# MMC-CAN.net
KiCad netlist of a schematic drawn in Altium Designer
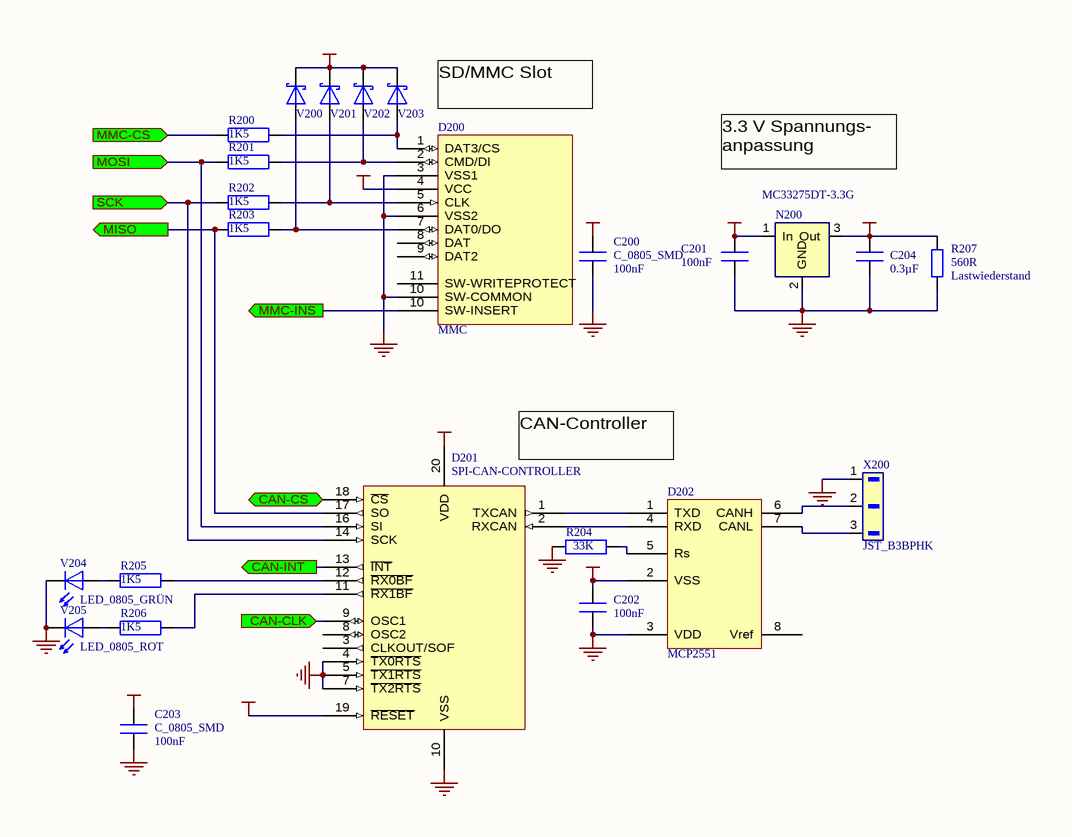
[diagram p0: MMC-CAN.SchDoc]

(export (version "E")
  (design (tool "Eeschema 10.0.6"))
  (components
    (comp (ref "C200")
      (value "C_0805_SMD")
      (footprint "0805_R")
      (description "Kondensator in SMD-Bauform")
      (fields (field (name "ALTIUM_UNNAMED_1") "100nF"))
      (libsource (lib "Kondensatoren") (part "C_0805_SMD"))
    )
    (comp (ref "C201")
      (value "C_0805_SMD")
      (footprint "0805_R")
      (description "Kondensator in SMD-Bauform")
      (fields (field (name "ALTIUM_UNNAMED_1") "100nF"))
      (libsource (lib "Kondensatoren") (part "C_0805_SMD"))
    )
    (comp (ref "C202")
      (value "C_0805_SMD")
      (footprint "0805_R")
      (description "Kondensator in SMD-Bauform")
      (fields (field (name "ALTIUM_UNNAMED_1") "100nF"))
      (libsource (lib "Kondensatoren") (part "C_0805_SMD"))
    )
    (comp (ref "C203")
      (value "C_0805_SMD")
      (footprint "0805_R")
      (description "Kondensator in SMD-Bauform")
      (fields (field (name "ALTIUM_UNNAMED_1") "100nF"))
      (libsource (lib "Kondensatoren") (part "C_0805_SMD"))
    )
    (comp (ref "C204")
      (value "C_1206_SMD")
      (footprint "1206_R")
      (description "Kondensator in SMD-Bauform")
      (fields (field (name "ALTIUM_UNNAMED_1") "0.3µF"))
      (libsource (lib "Kondensatoren") (part "C_1206_SMD"))
    )
    (comp (ref "D200") (value "MMC") (libsource (lib "Vorbereitung") (part "MMC")))
    (comp (ref "D201") (value "SPI-CAN-CONTROLLER") (libsource (lib "Vorbereitung") (part "MCP2515")))
    (comp (ref "D202") (value "MCP2551") (libsource (lib "Vorbereitung") (part "MCP2551")))
    (comp (ref "N200")
      (value "MC33275DT-3.3G")
      (footprint "DPAK_R")
      (description "MC33275DT-3.3G_SMD_3.3V Festspannungsregler positiv")
      (libsource (lib "Spannungsregler_SMD") (part "MC33275DT-3.3G_SMD"))
    )
    (comp (ref "R200")
      (value "R_0805_SMD")
      (footprint "0805_R")
      (description "Widerstand")
      (fields (field (name "ALTIUM_UNNAMED_1") "1K5"))
      (libsource (lib "Widerstände") (part "R_0805_SMD"))
    )
    (comp (ref "R201")
      (value "R_0805_SMD")
      (footprint "0805_R")
      (description "Widerstand")
      (fields (field (name "ALTIUM_UNNAMED_1") "1K5"))
      (libsource (lib "Widerstände") (part "R_0805_SMD"))
    )
    (comp (ref "R202")
      (value "R_0805_SMD")
      (footprint "0805_R")
      (description "Widerstand")
      (fields (field (name "ALTIUM_UNNAMED_1") "1K5"))
      (libsource (lib "Widerstände") (part "R_0805_SMD"))
    )
    (comp (ref "R203")
      (value "R_0805_SMD")
      (footprint "0805_R")
      (description "Widerstand")
      (fields (field (name "ALTIUM_UNNAMED_1") "1K5"))
      (libsource (lib "Widerstände") (part "R_0805_SMD"))
    )
    (comp (ref "R204")
      (value "R_0805_SMD")
      (footprint "0805_R")
      (description "Widerstand")
      (fields (field (name "ALTIUM_UNNAMED_1") "33K"))
      (libsource (lib "Widerstände") (part "R_0805_SMD"))
    )
    (comp (ref "R205")
      (value "R_0805_SMD")
      (footprint "0805_R")
      (description "Widerstand")
      (fields (field (name "ALTIUM_UNNAMED_1") "1K5"))
      (libsource (lib "Widerstände") (part "R_0805_SMD"))
    )
    (comp (ref "R206")
      (value "R_0805_SMD")
      (footprint "0805_R")
      (description "Widerstand")
      (fields (field (name "ALTIUM_UNNAMED_1") "1K5"))
      (libsource (lib "Widerstände") (part "R_0805_SMD"))
    )
    (comp (ref "R207")
      (value "Lastwiederstand")
      (footprint "CR2012-0805")
      (description "Resistor")
      (fields (field (name "ALTIUM_VALUE") "560R") (field (name "PUBLISHER") "Altium Limited"))
      (libsource (lib "Miscellaneous Devices") (part "Res2"))
    )
    (comp (ref "V200")
      (value "SCHOTTKY_SMC_SMD")
      (footprint "CR2012-0805")
      (description "SCHOTTKY-Diode_SMC_SMD")
      (libsource (lib "Dioden") (part "SCHOTTKY_SMC_SMD"))
    )
    (comp (ref "V201")
      (value "SCHOTTKY_SMC_SMD")
      (footprint "CR2012-0805")
      (description "SCHOTTKY-Diode_SMC_SMD")
      (libsource (lib "Dioden") (part "SCHOTTKY_SMC_SMD"))
    )
    (comp (ref "V202")
      (value "SCHOTTKY_SMC_SMD")
      (footprint "CR2012-0805")
      (description "SCHOTTKY-Diode_SMC_SMD")
      (libsource (lib "Dioden") (part "SCHOTTKY_SMC_SMD"))
    )
    (comp (ref "V203")
      (value "SCHOTTKY_SMC_SMD")
      (footprint "CR2012-0805")
      (description "SCHOTTKY-Diode_SMC_SMD")
      (libsource (lib "Dioden") (part "SCHOTTKY_SMC_SMD"))
    )
    (comp (ref "V204")
      (value "LED_0805_GRÜN")
      (footprint "0805_R")
      (description "Leuchtdiode_SMD_0805")
      (libsource (lib "Konventionel") (part "LED_0805_SMD"))
    )
    (comp (ref "V205")
      (value "LED_0805_ROT")
      (footprint "0805_R")
      (description "Leuchtdiode_SMD_0805")
      (libsource (lib "Konventionel") (part "LED_0805_SMD"))
    )
    (comp (ref "X200")
      (value "JST_B3BPHK")
      (footprint "B3BPHK")
      (description "Buchse_3-polig")
      (libsource (lib "Stecker") (part "JST_B3BPHK"))
    )
  )
  (nets
    (net (code "1") (name "/CAN-CLK") (class "Default")
      (node (ref "D201") (pin "9") (pinfunction "OSC1_9") (pintype "bidirectional"))
    )
    (net (code "2") (name "/CAN-CS") (class "Default")
      (node (ref "D201") (pin "18") (pinfunction "~{CS}_18") (pintype "input"))
    )
    (net (code "3") (name "/CAN-INT") (class "Default")
      (node (ref "D201") (pin "13") (pinfunction "~{INT}_13") (pintype "output"))
    )
    (net (code "4") (name "/MISO") (class "Default")
      (node (ref "D201") (pin "17") (pinfunction "SO_17") (pintype "output"))
      (node (ref "R203") (pin "1") (pinfunction "1_1") (pintype "passive"))
    )
    (net (code "5") (name "/MMC-CS") (class "Default")
      (node (ref "R200") (pin "1") (pinfunction "1_1") (pintype "passive"))
    )
    (net (code "6") (name "/MMC-INS") (class "Default")
      (node (ref "D200") (pin "10") (pinfunction "SW-INSERT_10") (pintype "passive"))
    )
    (net (code "7") (name "/MOSI") (class "Default")
      (node (ref "D201") (pin "16") (pinfunction "SI_16") (pintype "input"))
      (node (ref "R201") (pin "1") (pinfunction "1_1") (pintype "passive"))
    )
    (net (code "8") (name "/SCK") (class "Default")
      (node (ref "D201") (pin "14") (pinfunction "SCK_14") (pintype "input"))
      (node (ref "R202") (pin "1") (pinfunction "1_1") (pintype "passive"))
    )
    (net (code "9") (name "GND") (class "Default")
      (node (ref "C200") (pin "1") (pinfunction "1_1") (pintype "passive"))
      (node (ref "C201") (pin "2") (pinfunction "2_2") (pintype "passive"))
      (node (ref "C202") (pin "1") (pinfunction "1_1") (pintype "passive"))
      (node (ref "C203") (pin "1") (pinfunction "1_1") (pintype "passive"))
      (node (ref "C204") (pin "1") (pinfunction "1_1") (pintype "passive"))
      (node (ref "D200") (pin "10") (pinfunction "SW-COMMON_10") (pintype "passive"))
      (node (ref "D200") (pin "3") (pinfunction "VSS1_3") (pintype "power_in"))
      (node (ref "D200") (pin "6") (pinfunction "VSS2_6") (pintype "power_in"))
      (node (ref "D201") (pin "10") (pinfunction "VSS_10") (pintype "power_in"))
      (node (ref "D201") (pin "4") (pinfunction "~{TX0RTS}_4") (pintype "input"))
      (node (ref "D201") (pin "5") (pinfunction "~{TX1RTS}_5") (pintype "input"))
      (node (ref "D201") (pin "7") (pinfunction "~{TX2RTS}_7") (pintype "input"))
      (node (ref "D202") (pin "3") (pinfunction "VDD_3") (pintype "passive"))
      (node (ref "N200") (pin "2") (pinfunction "GND_2") (pintype "power_in"))
      (node (ref "R204") (pin "1") (pinfunction "1_1") (pintype "passive"))
      (node (ref "R207") (pin "2") (pinfunction "2_2") (pintype "passive"))
      (node (ref "V204") (pin "2") (pinfunction "K_2") (pintype "passive"))
      (node (ref "V205") (pin "2") (pinfunction "K_2") (pintype "passive"))
      (node (ref "X200") (pin "1") (pintype "passive"))
    )
    (net (code "10") (name "Net-(D200-CLK)") (class "Default")
      (node (ref "D200") (pin "5") (pinfunction "CLK_5") (pintype "input"))
      (node (ref "R202") (pin "2") (pinfunction "2_2") (pintype "passive"))
      (node (ref "V201") (pin "1") (pinfunction "A_1") (pintype "passive"))
    )
    (net (code "11") (name "Net-(D200-CMD{slash}DI)") (class "Default")
      (node (ref "D200") (pin "2") (pinfunction "CMD/DI_2") (pintype "bidirectional"))
      (node (ref "R201") (pin "2") (pinfunction "2_2") (pintype "passive"))
      (node (ref "V202") (pin "1") (pinfunction "A_1") (pintype "passive"))
    )
    (net (code "12") (name "Net-(D200-DAT0{slash}DO)") (class "Default")
      (node (ref "D200") (pin "7") (pinfunction "DAT0/DO_7") (pintype "bidirectional"))
      (node (ref "R203") (pin "2") (pinfunction "2_2") (pintype "passive"))
      (node (ref "V200") (pin "1") (pinfunction "A_1") (pintype "passive"))
    )
    (net (code "13") (name "Net-(D200-DAT3{slash}CS)") (class "Default")
      (node (ref "D200") (pin "1") (pinfunction "DAT3/CS_1") (pintype "bidirectional"))
      (node (ref "R200") (pin "2") (pinfunction "2_2") (pintype "passive"))
      (node (ref "V203") (pin "1") (pinfunction "A_1") (pintype "passive"))
    )
    (net (code "14") (name "Net-(D201-RXCAN)") (class "Default")
      (node (ref "D201") (pin "2") (pinfunction "RXCAN_2") (pintype "input"))
      (node (ref "D202") (pin "4") (pinfunction "RXD_4") (pintype "passive"))
    )
    (net (code "15") (name "Net-(D201-TXCAN)") (class "Default")
      (node (ref "D201") (pin "1") (pinfunction "TXCAN_1") (pintype "output"))
      (node (ref "D202") (pin "1") (pinfunction "TXD_1") (pintype "passive"))
    )
    (net (code "16") (name "Net-(D201-~{RX0BF})") (class "Default")
      (node (ref "D201") (pin "12") (pinfunction "~{RX0BF}_12") (pintype "output"))
      (node (ref "R205") (pin "2") (pinfunction "2_2") (pintype "passive"))
    )
    (net (code "17") (name "Net-(D201-~{RX1BF})") (class "Default")
      (node (ref "D201") (pin "11") (pinfunction "~{RX1BF}_11") (pintype "output"))
      (node (ref "R206") (pin "2") (pinfunction "2_2") (pintype "passive"))
    )
    (net (code "18") (name "Net-(D202-CANH)") (class "Default")
      (node (ref "D202") (pin "6") (pinfunction "CANH_6") (pintype "passive"))
      (node (ref "X200") (pin "2") (pintype "passive"))
    )
    (net (code "19") (name "Net-(D202-CANL)") (class "Default")
      (node (ref "D202") (pin "7") (pinfunction "CANL_7") (pintype "passive"))
      (node (ref "X200") (pin "3") (pintype "passive"))
    )
    (net (code "20") (name "Net-(D202-Rs)") (class "Default")
      (node (ref "D202") (pin "5") (pinfunction "Rs_5") (pintype "passive"))
      (node (ref "R204") (pin "2") (pinfunction "2_2") (pintype "passive"))
    )
    (net (code "21") (name "Net-(V204-A)") (class "Default")
      (node (ref "R205") (pin "1") (pinfunction "1_1") (pintype "passive"))
      (node (ref "V204") (pin "1") (pinfunction "A_1") (pintype "passive"))
    )
    (net (code "22") (name "Net-(V205-A)") (class "Default")
      (node (ref "R206") (pin "1") (pinfunction "1_1") (pintype "passive"))
      (node (ref "V205") (pin "1") (pinfunction "A_1") (pintype "passive"))
    )
    (net (code "23") (name "VCC") (class "Default")
      (node (ref "C200") (pin "2") (pinfunction "2_2") (pintype "passive"))
      (node (ref "C201") (pin "1") (pinfunction "1_1") (pintype "passive"))
      (node (ref "C202") (pin "2") (pinfunction "2_2") (pintype "passive"))
      (node (ref "C203") (pin "2") (pinfunction "2_2") (pintype "passive"))
      (node (ref "D201") (pin "19") (pinfunction "~{RESET}_19") (pintype "input"))
      (node (ref "D201") (pin "20") (pinfunction "VDD_20") (pintype "power_in"))
      (node (ref "D202") (pin "2") (pinfunction "VSS_2") (pintype "passive"))
      (node (ref "N200") (pin "1") (pinfunction "In_1") (pintype "power_in"))
    )
    (net (code "24") (name "VCC3V") (class "Default")
      (node (ref "C204") (pin "2") (pinfunction "2_2") (pintype "passive"))
      (node (ref "D200") (pin "4") (pinfunction "VCC_4") (pintype "power_in"))
      (node (ref "N200") (pin "3") (pinfunction "Out_3") (pintype "power_in"))
      (node (ref "R207") (pin "1") (pinfunction "1_1") (pintype "passive"))
      (node (ref "V200") (pin "2") (pinfunction "K_2") (pintype "passive"))
      (node (ref "V201") (pin "2") (pinfunction "K_2") (pintype "passive"))
      (node (ref "V202") (pin "2") (pinfunction "K_2") (pintype "passive"))
      (node (ref "V203") (pin "2") (pinfunction "K_2") (pintype "passive"))
    )
    (net (code "25") (name "unconnected-(D200-DAT-Pad8)") (class "Default")
      (node (ref "D200") (pin "8") (pinfunction "DAT_8") (pintype "bidirectional"))
    )
    (net (code "26") (name "unconnected-(D200-DAT2-Pad9)") (class "Default")
      (node (ref "D200") (pin "9") (pinfunction "DAT2_9") (pintype "bidirectional"))
    )
    (net (code "27") (name "unconnected-(D200-SW-WRITEPROTECT-Pad11)") (class "Default")
      (node (ref "D200") (pin "11") (pinfunction "SW-WRITEPROTECT_11") (pintype "passive"))
    )
    (net (code "28") (name "unconnected-(D201-CLKOUT{slash}SOF-Pad3)") (class "Default")
      (node (ref "D201") (pin "3") (pinfunction "CLKOUT/SOF_3") (pintype "output"))
    )
    (net (code "29") (name "unconnected-(D201-OSC2-Pad8)") (class "Default")
      (node (ref "D201") (pin "8") (pinfunction "OSC2_8") (pintype "bidirectional"))
    )
    (net (code "30") (name "unconnected-(D202-Vref-Pad8)") (class "Default")
      (node (ref "D202") (pin "8") (pinfunction "Vref_8") (pintype "passive"))
    )
  )
)
